# Sheet1.net
KiCad netlist of a schematic drawn in Altium Designer
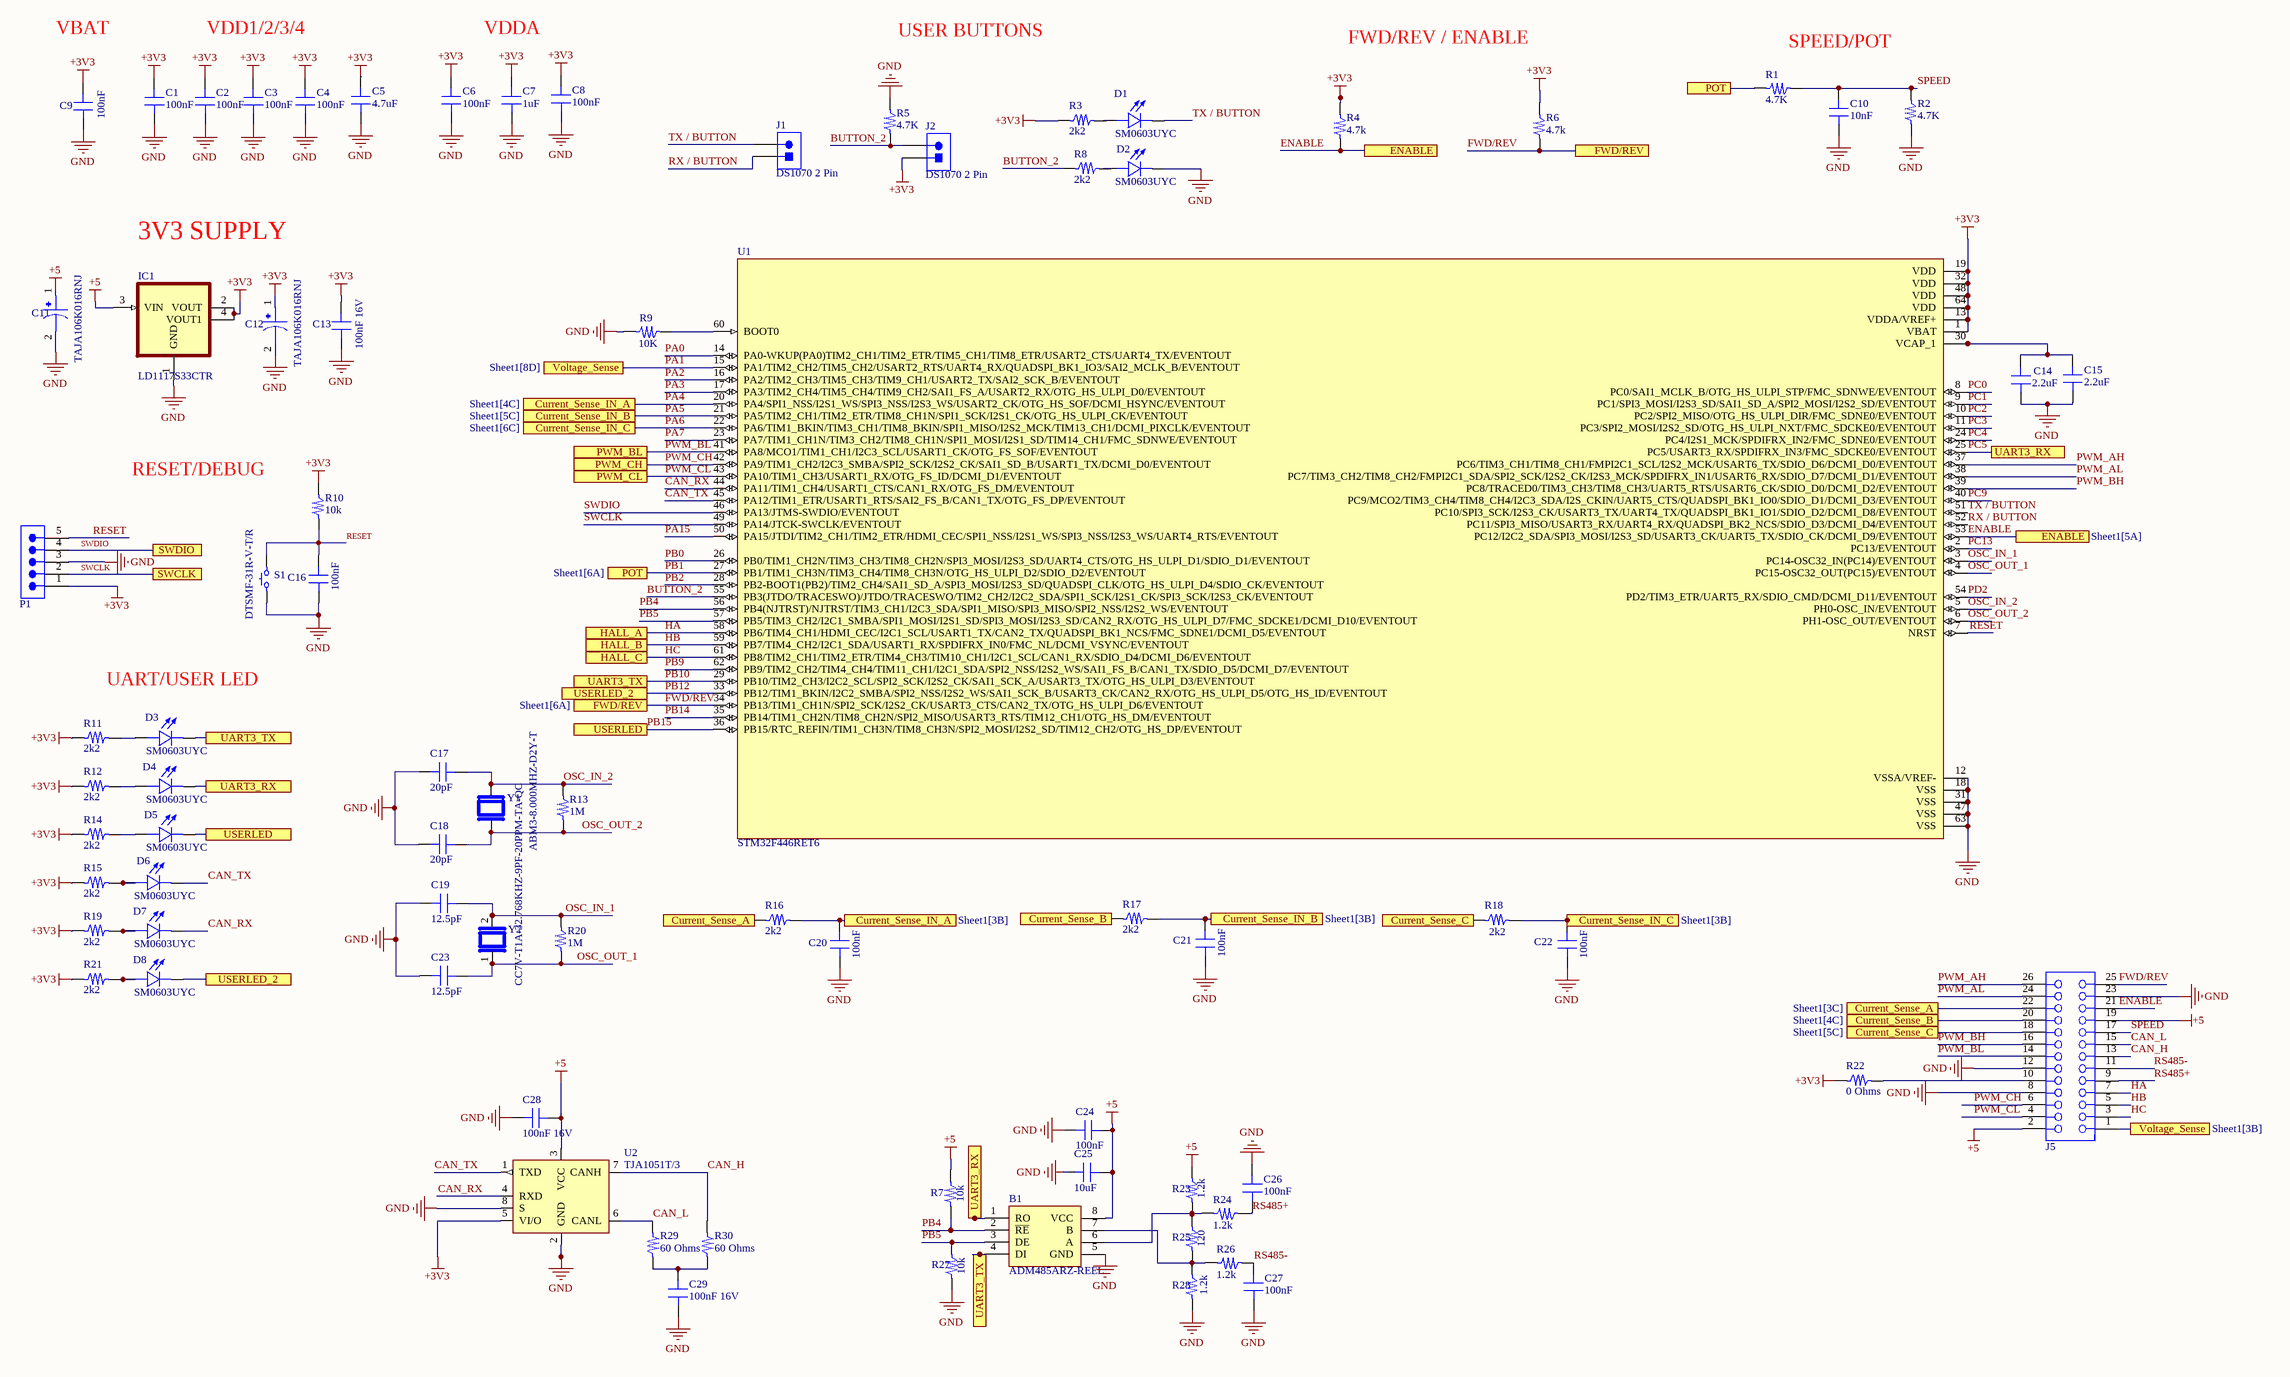
[diagram p0: Sheet1.SchDoc]

(export (version "E")
  (design (tool "Eeschema 10.0.6"))
  (components
    (comp (ref "B1")
      (value "ADM485ARZ-REEL")
      (footprint "SOIC127P600X175-8N")
      (description "RS-422/RS-485 Interface IC RS-485 I/F TRANSCEIVER")
      (fields (field (name "MOUSER PART NUMBER") "584-ADM485ARZ-R"))
      (libsource (lib "ADM485ARZ-REEL") (part "ADM485ARZ-REEL"))
    )
    (comp (ref "C1")
      (value "100nF")
      (footprint "0603_CAP")
      (description "CL10B105KO8NNNC - MLCC (1608) 0603 1uF 16VDC ±10% X7R")
      (libsource (lib "HidroanaSCHLib1") (part "CAP_0603"))
    )
    (comp (ref "C2")
      (value "100nF")
      (footprint "0603_CAP")
      (description "CL10B105KO8NNNC - MLCC (1608) 0603 1uF 16VDC ±10% X7R")
      (libsource (lib "HidroanaSCHLib1") (part "CAP_0603"))
    )
    (comp (ref "C3")
      (value "100nF")
      (footprint "0603_CAP")
      (description "CL10B105KO8NNNC - MLCC (1608) 0603 1uF 16VDC ±10% X7R")
      (libsource (lib "HidroanaSCHLib1") (part "CAP_0603"))
    )
    (comp (ref "C4")
      (value "100nF")
      (footprint "0603_CAP")
      (description "CL10B105KO8NNNC - MLCC (1608) 0603 1uF 16VDC ±10% X7R")
      (libsource (lib "HidroanaSCHLib1") (part "CAP_0603"))
    )
    (comp (ref "C5")
      (value "4.7uF")
      (footprint "0603_CAP")
      (description "CL10B105KO8NNNC - MLCC (1608) 0603 1uF 16VDC ±10% X7R")
      (libsource (lib "HidroanaSCHLib1") (part "CAP_0603"))
    )
    (comp (ref "C6")
      (value "100nF")
      (footprint "0603_CAP")
      (description "CL10B105KO8NNNC - MLCC (1608) 0603 1uF 16VDC ±10% X7R")
      (libsource (lib "HidroanaSCHLib1") (part "CAP_0603"))
    )
    (comp (ref "C7")
      (value "1uF")
      (footprint "0603_CAP")
      (description "CL10B105KO8NNNC - MLCC (1608) 0603 1uF 16VDC ±10% X7R")
      (libsource (lib "HidroanaSCHLib1") (part "CAP_0603"))
    )
    (comp (ref "C8")
      (value "100nF")
      (footprint "0603_CAP")
      (description "CL10B105KO8NNNC - MLCC (1608) 0603 1uF 16VDC ±10% X7R")
      (libsource (lib "HidroanaSCHLib1") (part "CAP_0603"))
    )
    (comp (ref "C9")
      (value "100nF")
      (footprint "0603_CAP")
      (description "CL10B105KO8NNNC - MLCC (1608) 0603 1uF 16VDC ±10% X7R")
      (libsource (lib "HidroanaSCHLib1") (part "CAP_0603"))
    )
    (comp (ref "C10")
      (value "10nF")
      (footprint "0603_CAP")
      (description "CL10B105KO8NNNC - MLCC (1608) 0603 1uF 16VDC ±10% X7R")
      (libsource (lib "HidroanaSCHLib1") (part "CAP_0603"))
    )
    (comp (ref "C11")
      (value "TAJA106K016RNJ")
      (footprint "CAPMP3216X180N")
      (description "10ÂµF Molded Tantalum Capacitors 16V 1206 (3216 Metric) 3Ohm")
      (fields (field (name "MF") "AVX"))
      (libsource (lib "TAJA106K016RNJ") (part "TAJA106K016RNJ"))
    )
    (comp (ref "C12")
      (value "TAJA106K016RNJ")
      (footprint "CAPMP3216X180N")
      (description "10ÂµF Molded Tantalum Capacitors 16V 1206 (3216 Metric) 3Ohm")
      (fields (field (name "MF") "AVX"))
      (libsource (lib "TAJA106K016RNJ") (part "TAJA106K016RNJ"))
    )
    (comp (ref "C13")
      (value "100nF 16V")
      (footprint "0805_CAP")
      (libsource (lib "HidroanaSCHLib") (part "CAP_0805"))
    )
    (comp (ref "C14")
      (value "2.2uF")
      (footprint "0603_CAP")
      (description "CL10B105KO8NNNC - MLCC (1608) 0603 1uF 16VDC ±10% X7R")
      (libsource (lib "HidroanaSCHLib1") (part "CAP_0603"))
    )
    (comp (ref "C15")
      (value "2.2uF")
      (footprint "0603_CAP")
      (description "CL10B105KO8NNNC - MLCC (1608) 0603 1uF 16VDC ±10% X7R")
      (libsource (lib "HidroanaSCHLib1") (part "CAP_0603"))
    )
    (comp (ref "C16")
      (value "100nF")
      (footprint "0603_CAP")
      (description "CL10B105KO8NNNC - MLCC (1608) 0603 1uF 16VDC ±10% X7R")
      (libsource (lib "HidroanaSCHLib1") (part "CAP_0603"))
    )
    (comp (ref "C17")
      (value "20pF")
      (footprint "0603_CAP")
      (description "CL10B105KO8NNNC - MLCC (1608) 0603 1uF 16VDC ±10% X7R")
      (libsource (lib "HidroanaSCHLib1") (part "CAP_0603"))
    )
    (comp (ref "C18")
      (value "20pF")
      (footprint "0603_CAP")
      (description "CL10B105KO8NNNC - MLCC (1608) 0603 1uF 16VDC ±10% X7R")
      (libsource (lib "HidroanaSCHLib1") (part "CAP_0603"))
    )
    (comp (ref "C19")
      (value "12.5pF")
      (footprint "0603_CAP")
      (description "CL10B105KO8NNNC - MLCC (1608) 0603 1uF 16VDC ±10% X7R")
      (libsource (lib "HidroanaSCHLib1") (part "CAP_0603"))
    )
    (comp (ref "C20")
      (value "100nF")
      (footprint "0603_CAP")
      (description "CL10B105KO8NNNC - MLCC (1608) 0603 1uF 16VDC ±10% X7R")
      (libsource (lib "HidroanaSCHLib1") (part "CAP_0603"))
    )
    (comp (ref "C21")
      (value "100nF")
      (footprint "0603_CAP")
      (description "CL10B105KO8NNNC - MLCC (1608) 0603 1uF 16VDC ±10% X7R")
      (libsource (lib "HidroanaSCHLib1") (part "CAP_0603"))
    )
    (comp (ref "C22")
      (value "100nF")
      (footprint "0603_CAP")
      (description "CL10B105KO8NNNC - MLCC (1608) 0603 1uF 16VDC ±10% X7R")
      (libsource (lib "HidroanaSCHLib1") (part "CAP_0603"))
    )
    (comp (ref "C23")
      (value "12.5pF")
      (footprint "0603_CAP")
      (description "CL10B105KO8NNNC - MLCC (1608) 0603 1uF 16VDC ±10% X7R")
      (libsource (lib "HidroanaSCHLib1") (part "CAP_0603"))
    )
    (comp (ref "C24")
      (value "100nF")
      (footprint "0603_CAP")
      (description "CL10B105KO8NNNC - MLCC (1608) 0603 1uF 16VDC ±10% X7R")
      (libsource (lib "HidroanaSCHLib1") (part "CAP_0603"))
    )
    (comp (ref "C25")
      (value "10uF")
      (footprint "0603_CAP")
      (description "CL10B105KO8NNNC - MLCC (1608) 0603 1uF 16VDC ±10% X7R")
      (libsource (lib "HidroanaSCHLib1") (part "CAP_0603"))
    )
    (comp (ref "C26")
      (value "100nF")
      (footprint "0603_CAP")
      (description "CL10B105KO8NNNC - MLCC (1608) 0603 1uF 16VDC ±10% X7R")
      (libsource (lib "HidroanaSCHLib1") (part "CAP_0603"))
    )
    (comp (ref "C27")
      (value "100nF")
      (footprint "0603_CAP")
      (description "CL10B105KO8NNNC - MLCC (1608) 0603 1uF 16VDC ±10% X7R")
      (libsource (lib "HidroanaSCHLib1") (part "CAP_0603"))
    )
    (comp (ref "C28")
      (value "100nF 16V")
      (footprint "0603_CAP")
      (description "CL10B105KO8NNNC - MLCC (1608) 0603 1uF 16VDC ±10% X7R")
      (libsource (lib "HidroanaSCHLib") (part "CAP_0603"))
    )
    (comp (ref "C29")
      (value "100nF 16V")
      (footprint "0603_CAP")
      (description "CL10B105KO8NNNC - MLCC (1608) 0603 1uF 16VDC ±10% X7R")
      (libsource (lib "HidroanaSCHLib") (part "CAP_0603"))
    )
    (comp (ref "D1")
      (value "SM0603UYC")
      (footprint "LED_SM0603UYC")
      (fields (field (name "MF") "Bivar"))
      (libsource (lib "SM0603UYC") (part "SM0603UYC"))
    )
    (comp (ref "D2")
      (value "SM0603UYC")
      (footprint "LED_SM0603UYC")
      (fields (field (name "MF") "Bivar"))
      (libsource (lib "SM0603UYC") (part "SM0603UYC"))
    )
    (comp (ref "D3")
      (value "SM0603UYC")
      (footprint "LED_SM0603UYC")
      (fields (field (name "MF") "Bivar"))
      (libsource (lib "SM0603UYC") (part "SM0603UYC"))
    )
    (comp (ref "D4")
      (value "SM0603UYC")
      (footprint "LED_SM0603UYC")
      (fields (field (name "MF") "Bivar"))
      (libsource (lib "SM0603UYC") (part "SM0603UYC"))
    )
    (comp (ref "D5")
      (value "SM0603UYC")
      (footprint "LED_SM0603UYC")
      (fields (field (name "MF") "Bivar"))
      (libsource (lib "SM0603UYC") (part "SM0603UYC"))
    )
    (comp (ref "D6")
      (value "SM0603UYC")
      (footprint "LED_SM0603UYC")
      (fields (field (name "MF") "Bivar"))
      (libsource (lib "SM0603UYC") (part "SM0603UYC"))
    )
    (comp (ref "D7")
      (value "SM0603UYC")
      (footprint "LED_SM0603UYC")
      (fields (field (name "MF") "Bivar"))
      (libsource (lib "SM0603UYC") (part "SM0603UYC"))
    )
    (comp (ref "D8")
      (value "SM0603UYC")
      (footprint "LED_SM0603UYC")
      (fields (field (name "MF") "Bivar"))
      (libsource (lib "SM0603UYC") (part "SM0603UYC"))
    )
    (comp (ref "IC1")
      (value "LD1117S33CTR")
      (footprint "SOT223")
      (description "Linear Voltage Regulator IC Positive Fixed 1 Output 800mA SOT-223")
      (fields (field (name "MF") "STMicroelectronics"))
      (libsource (lib "LD1117S33CTR") (part "LD1117S33CTR"))
    )
    (comp (ref "J1")
      (value "DS1070 2 Pin")
      (footprint "2PIN_100mil")
      (description "2pin Socket 100mil")
      (libsource (lib "HidroanaSCHLib1") (part "2 Pin Socket"))
    )
    (comp (ref "J2")
      (value "DS1070 2 Pin")
      (footprint "2PIN_100mil")
      (description "2pin Socket 100mil")
      (libsource (lib "HidroanaSCHLib1") (part "2 Pin Socket"))
    )
    (comp (ref "J5")
      (value "61302621821")
      (footprint "61302621821")
      (description "WR-PHD Socket Header, THT, Vertical, pitch 2.54mm, 2 Row, 26P")
      (fields (field (name "MANUFACTURER") "Wurth Elektronik"))
      (libsource (lib "Altium_WR-PHD (rev24a) (3)") (part "61302621821"))
    )
    (comp (ref "P1")
      (value "61300511121")
      (footprint "61300511121")
      (description "WR-PHD Pin Header, THT, Vertical, pitch 2.54mm, 1 Row, 5P")
      (fields (field (name "MANUFACTURER") "Wurth Elektronik"))
      (libsource (lib "Altium_WR-PHD (rev24a)") (part "61300511121"))
    )
    (comp (ref "R1")
      (value "4.7K")
      (footprint "0603_RES")
      (description "0603")
      (fields (field (name "POWER") "1/8W"))
      (libsource (lib "HidroanaSCHLib") (part "RES_0603"))
    )
    (comp (ref "R2")
      (value "4.7K")
      (footprint "0603_RES")
      (description "0603")
      (fields (field (name "POWER") "1/8W"))
      (libsource (lib "HidroanaSCHLib") (part "RES_0603"))
    )
    (comp (ref "R3")
      (value "2k2")
      (footprint "0603_RES")
      (description "0603")
      (fields (field (name "POWER") "1/8W"))
      (libsource (lib "HidroanaSCHLib") (part "RES_0603"))
    )
    (comp (ref "R4")
      (value "4.7k")
      (footprint "0603_RES")
      (description "0603")
      (fields (field (name "POWER") "1/8W"))
      (libsource (lib "HidroanaSCHLib") (part "RES_0603"))
    )
    (comp (ref "R5")
      (value "4.7K")
      (footprint "0603_RES")
      (description "0603")
      (fields (field (name "POWER") "1/8W"))
      (libsource (lib "HidroanaSCHLib") (part "RES_0603"))
    )
    (comp (ref "R6")
      (value "4.7k")
      (footprint "0603_RES")
      (description "0603")
      (fields (field (name "POWER") "1/8W"))
      (libsource (lib "HidroanaSCHLib") (part "RES_0603"))
    )
    (comp (ref "R7")
      (value "10k")
      (footprint "0603_RES")
      (description "0603")
      (fields (field (name "POWER") "1/8W"))
      (libsource (lib "HidroanaSCHLib") (part "RES_0603"))
    )
    (comp (ref "R8")
      (value "2k2")
      (footprint "0603_RES")
      (description "0603")
      (fields (field (name "POWER") "1/8W"))
      (libsource (lib "HidroanaSCHLib") (part "RES_0603"))
    )
    (comp (ref "R9")
      (value "10K")
      (footprint "0603_RES")
      (description "0603")
      (fields (field (name "POWER") "1/8W"))
      (libsource (lib "HidroanaSCHLib") (part "RES_0603"))
    )
    (comp (ref "R10")
      (value "10k")
      (footprint "0603_RES")
      (description "0603")
      (fields (field (name "POWER") "1/8W"))
      (libsource (lib "HidroanaSCHLib") (part "RES_0603"))
    )
    (comp (ref "R11")
      (value "2k2")
      (footprint "0603_RES")
      (description "0603")
      (fields (field (name "POWER") "1/8W"))
      (libsource (lib "HidroanaSCHLib") (part "RES_0603"))
    )
    (comp (ref "R12")
      (value "2k2")
      (footprint "0603_RES")
      (description "0603")
      (fields (field (name "POWER") "1/8W"))
      (libsource (lib "HidroanaSCHLib") (part "RES_0603"))
    )
    (comp (ref "R13")
      (value "1M")
      (footprint "0603_RES")
      (description "0603")
      (fields (field (name "POWER") "1/8W"))
      (libsource (lib "HidroanaSCHLib") (part "RES_0603"))
    )
    (comp (ref "R14")
      (value "2k2")
      (footprint "0603_RES")
      (description "0603")
      (fields (field (name "POWER") "1/8W"))
      (libsource (lib "HidroanaSCHLib") (part "RES_0603"))
    )
    (comp (ref "R15")
      (value "2k2")
      (footprint "0603_RES")
      (description "0603")
      (fields (field (name "POWER") "1/8W"))
      (libsource (lib "HidroanaSCHLib") (part "RES_0603"))
    )
    (comp (ref "R16")
      (value "2k2")
      (footprint "0603_RES")
      (description "0603")
      (fields (field (name "POWER") "1/8W"))
      (libsource (lib "HidroanaSCHLib") (part "RES_0603"))
    )
    (comp (ref "R17")
      (value "2k2")
      (footprint "0603_RES")
      (description "0603")
      (fields (field (name "POWER") "1/8W"))
      (libsource (lib "HidroanaSCHLib") (part "RES_0603"))
    )
    (comp (ref "R18")
      (value "2k2")
      (footprint "0603_RES")
      (description "0603")
      (fields (field (name "POWER") "1/8W"))
      (libsource (lib "HidroanaSCHLib") (part "RES_0603"))
    )
    (comp (ref "R19")
      (value "2k2")
      (footprint "0603_RES")
      (description "0603")
      (fields (field (name "POWER") "1/8W"))
      (libsource (lib "HidroanaSCHLib") (part "RES_0603"))
    )
    (comp (ref "R20")
      (value "1M")
      (footprint "0603_RES")
      (description "0603")
      (fields (field (name "POWER") "1/8W"))
      (libsource (lib "HidroanaSCHLib") (part "RES_0603"))
    )
    (comp (ref "R21")
      (value "2k2")
      (footprint "0603_RES")
      (description "0603")
      (fields (field (name "POWER") "1/8W"))
      (libsource (lib "HidroanaSCHLib") (part "RES_0603"))
    )
    (comp (ref "R22")
      (value "0 Ohms")
      (footprint "0805_RES")
      (description "0805")
      (fields (field (name "POWER") "1/8 W"))
      (libsource (lib "HidroanaSCHLib") (part "RES_0805"))
    )
    (comp (ref "R23")
      (value "1.2k")
      (footprint "0603_RES")
      (description "0603")
      (fields (field (name "POWER") "1/8W"))
      (libsource (lib "HidroanaSCHLib") (part "RES_0603"))
    )
    (comp (ref "R24")
      (value "1.2k")
      (footprint "0603_RES")
      (description "0603")
      (fields (field (name "POWER") "1/8W"))
      (libsource (lib "HidroanaSCHLib") (part "RES_0603"))
    )
    (comp (ref "R25")
      (value "120")
      (footprint "0603_RES")
      (description "0603")
      (fields (field (name "POWER") "1/8W"))
      (libsource (lib "HidroanaSCHLib") (part "RES_0603"))
    )
    (comp (ref "R26")
      (value "1.2k")
      (footprint "0603_RES")
      (description "0603")
      (fields (field (name "POWER") "1/8W"))
      (libsource (lib "HidroanaSCHLib") (part "RES_0603"))
    )
    (comp (ref "R27")
      (value "10k")
      (footprint "0603_RES")
      (description "0603")
      (fields (field (name "POWER") "1/8W"))
      (libsource (lib "HidroanaSCHLib") (part "RES_0603"))
    )
    (comp (ref "R28")
      (value "1.2k")
      (footprint "0603_RES")
      (description "0603")
      (fields (field (name "POWER") "1/8W"))
      (libsource (lib "HidroanaSCHLib") (part "RES_0603"))
    )
    (comp (ref "R29")
      (value "60 Ohms")
      (footprint "0603_RES")
      (libsource (lib "HidroanaSCHLib") (part "1k Ohms"))
    )
    (comp (ref "R30")
      (value "60 Ohms")
      (footprint "0603_RES")
      (libsource (lib "HidroanaSCHLib") (part "1k Ohms"))
    )
    (comp (ref "S1")
      (value "DTSMF-31R-V-T/R")
      (footprint "Button")
      (description "DTSMF-31R-V-T/R - SWITCH TACT 6.00x3.50 4.30mm 260gF SMT V/T")
      (libsource (lib "HidroanaSCHLib") (part "DTSMF-31R-V-T/R"))
    )
    (comp (ref "U1")
      (value "STM32F446RET6")
      (footprint "QFP50P1200X1200X160-64N")
      (description "MCU 32-Bit STM32 ARM Cortex M4 RISC 512KB Flash 2.5V/3.3V 64-Pin LQFP Tray")
      (libsource (lib "STM32F446RET6") (part "STM32F446RET6"))
    )
    (comp (ref "U2")
      (value "TJA1051T/3")
      (footprint "SOT96-1")
      (description "1/1 ÐŸÑ€Ð¸ÐµÐ¼Ð¾Ð¿ÐµÑ€ÐµÐ´Ð°Ñ‚Ñ‡Ð¸Ðº ÐŸÐ¾Ð»Ð¾Ð²Ð¸Ð½Ð° CANbus 8-SO")
      (fields (field (name "MF") "NXP USA"))
      (libsource (lib "TJA1051T_3") (part "TJA1051T/3"))
    )
    (comp (ref "Y1")
      (value "ABM3-8.000MHZ-D2Y-T")
      (footprint "XTAL_ABM3-8.000MHZ-D2Y-T")
      (description "8 MHz Â±20ppm Crystal 18pF 140 Ohms 2-SMD, No Lead")
      (fields (field (name "MF") "Abracon"))
      (libsource (lib "ABM3-8.000MHZ-D2Y-T") (part "ABM3-8.000MHZ-D2Y-T"))
    )
    (comp (ref "Y2")
      (value "CC7V-T1A-32.768KHZ-9PF-20PPM-TA-QC")
      (footprint "XTAL_CC7V-T1A-32.768KHZ-9PF-20PPM-TA-QC")
      (description "LOW FREQUENCY CRYSTAL")
      (fields (field (name "MF") "Micro Crystal") (field (name "MP") "CC7V-T1A-32.768kHz-9pF-20PPM-TA-QC"))
      (libsource (lib "CC7V-T1A-32.768KHZ-9PF-20PPM-TA-QC") (part "CC7V-T1A-32.768KHZ-9PF-20PPM-TA-QC"))
    )
  )
  (nets
    (net (code "1") (name "+3V3") (class "Default")
      (node (ref "C1") (pin "1") (pinfunction "1_1") (pintype "passive"))
      (node (ref "C12") (pin "1") (pinfunction "1_1") (pintype "passive"))
      (node (ref "C13") (pin "2") (pinfunction "2_2") (pintype "passive"))
      (node (ref "C2") (pin "1") (pinfunction "1_1") (pintype "passive"))
      (node (ref "C3") (pin "1") (pinfunction "1_1") (pintype "passive"))
      (node (ref "C4") (pin "1") (pinfunction "1_1") (pintype "passive"))
      (node (ref "C5") (pin "1") (pinfunction "1_1") (pintype "passive"))
      (node (ref "C6") (pin "1") (pinfunction "1_1") (pintype "passive"))
      (node (ref "C7") (pin "1") (pinfunction "1_1") (pintype "passive"))
      (node (ref "C8") (pin "1") (pinfunction "1_1") (pintype "passive"))
      (node (ref "C9") (pin "1") (pinfunction "1_1") (pintype "passive"))
      (node (ref "IC1") (pin "2") (pinfunction "VOUT_2") (pintype "power_in"))
      (node (ref "IC1") (pin "4") (pinfunction "VOUT1_4") (pintype "power_in"))
      (node (ref "J2") (pin "1") (pintype "passive"))
      (node (ref "P1") (pin "1") (pinfunction "1_1") (pintype "passive"))
      (node (ref "R10") (pin "2") (pintype "passive"))
      (node (ref "R11") (pin "1") (pintype "passive"))
      (node (ref "R12") (pin "1") (pintype "passive"))
      (node (ref "R14") (pin "1") (pintype "passive"))
      (node (ref "R15") (pin "1") (pintype "passive"))
      (node (ref "R19") (pin "1") (pintype "passive"))
      (node (ref "R21") (pin "1") (pintype "passive"))
      (node (ref "R22") (pin "1") (pintype "passive"))
      (node (ref "R3") (pin "1") (pintype "passive"))
      (node (ref "R4") (pin "2") (pintype "passive"))
      (node (ref "R6") (pin "2") (pintype "passive"))
      (node (ref "U1") (pin "1") (pinfunction "VBAT_1") (pintype "power_in"))
      (node (ref "U1") (pin "13") (pinfunction "VDDA/VREF+_13") (pintype "power_in"))
      (node (ref "U1") (pin "19") (pinfunction "VDD_19") (pintype "power_in"))
      (node (ref "U1") (pin "32") (pinfunction "VDD_32") (pintype "power_in"))
      (node (ref "U1") (pin "48") (pinfunction "VDD_48") (pintype "power_in"))
      (node (ref "U1") (pin "64") (pinfunction "VDD_64") (pintype "power_in"))
      (node (ref "U2") (pin "5") (pinfunction "VI/O_5") (pintype "passive"))
    )
    (net (code "2") (name "+5") (class "Default")
      (node (ref "B1") (pin "8") (pinfunction "VCC_8") (pintype "passive"))
      (node (ref "C11") (pin "1") (pinfunction "1_1") (pintype "passive"))
      (node (ref "C24") (pin "1") (pinfunction "1_1") (pintype "passive"))
      (node (ref "C25") (pin "1") (pinfunction "1_1") (pintype "passive"))
      (node (ref "C28") (pin "2") (pinfunction "2_2") (pintype "passive"))
      (node (ref "IC1") (pin "3") (pinfunction "VIN_3") (pintype "input"))
      (node (ref "J5") (pin "19") (pinfunction "19_19") (pintype "passive"))
      (node (ref "J5") (pin "2") (pinfunction "2_2") (pintype "passive"))
      (node (ref "R23") (pin "2") (pintype "passive"))
      (node (ref "R7") (pin "2") (pintype "passive"))
      (node (ref "U2") (pin "3") (pinfunction "VCC_3") (pintype "bidirectional"))
    )
    (net (code "3") (name "/BUTTON_2") (class "Default")
      (node (ref "J2") (pin "2") (pinfunction "2_2") (pintype "passive"))
      (node (ref "R5") (pin "1") (pintype "passive"))
      (node (ref "R8") (pin "1") (pintype "passive"))
      (node (ref "U1") (pin "55") (pinfunction "PB3(JTDO/TRACESWO)/JTDO/TRACESWO/TIM2_CH2/I2C2_SDA/SPI1_SCK/I2S1_CK/SPI3_SCK/I2S3_CK/EVENTOUT_55") (pintype "bidirectional"))
    )
    (net (code "4") (name "/CAN_H") (class "Default")
      (node (ref "J5") (pin "13") (pinfunction "13_13") (pintype "passive"))
      (node (ref "R30") (pin "1") (pintype "passive"))
      (node (ref "U2") (pin "7") (pinfunction "CANH_7") (pintype "bidirectional"))
    )
    (net (code "5") (name "/CAN_L") (class "Default")
      (node (ref "J5") (pin "15") (pinfunction "15_15") (pintype "passive"))
      (node (ref "R29") (pin "1") (pintype "passive"))
      (node (ref "U2") (pin "6") (pinfunction "CANL_6") (pintype "bidirectional"))
    )
    (net (code "6") (name "/CAN_RX") (class "Default")
      (node (ref "D7") (pin "C") (pinfunction "C_C") (pintype "passive"))
      (node (ref "U1") (pin "44") (pinfunction "PA11/TIM1_CH4/USART1_CTS/CAN1_RX/OTG_FS_DM/EVENTOUT_44") (pintype "bidirectional"))
      (node (ref "U2") (pin "4") (pinfunction "RXD_4") (pintype "bidirectional"))
    )
    (net (code "7") (name "/CAN_TX") (class "Default")
      (node (ref "D6") (pin "C") (pinfunction "C_C") (pintype "passive"))
      (node (ref "U1") (pin "45") (pinfunction "PA12/TIM1_ETR/USART1_RTS/SAI2_FS_B/CAN1_TX/OTG_FS_DP/EVENTOUT_45") (pintype "bidirectional"))
      (node (ref "U2") (pin "1") (pinfunction "TXD_1") (pintype "output"))
    )
    (net (code "8") (name "/Current_Sense_A") (class "Default")
      (node (ref "J5") (pin "22") (pinfunction "22_22") (pintype "passive"))
      (node (ref "R16") (pin "1") (pintype "passive"))
    )
    (net (code "9") (name "/Current_Sense_B") (class "Default")
      (node (ref "J5") (pin "20") (pinfunction "20_20") (pintype "passive"))
      (node (ref "R17") (pin "1") (pintype "passive"))
    )
    (net (code "10") (name "/Current_Sense_C") (class "Default")
      (node (ref "J5") (pin "18") (pinfunction "18_18") (pintype "passive"))
      (node (ref "R18") (pin "1") (pintype "passive"))
    )
    (net (code "11") (name "/ENABLE") (class "Default")
      (node (ref "J5") (pin "21") (pinfunction "21_21") (pintype "passive"))
      (node (ref "R4") (pin "1") (pintype "passive"))
      (node (ref "U1") (pin "53") (pinfunction "PC12/I2C2_SDA/SPI3_MOSI/I2S3_SD/USART3_CK/UART5_TX/SDIO_CK/DCMI_D9/EVENTOUT_53") (pintype "bidirectional"))
    )
    (net (code "12") (name "/FWD{slash}REV") (class "Default")
      (node (ref "J5") (pin "25") (pinfunction "25_25") (pintype "passive"))
      (node (ref "R6") (pin "1") (pintype "passive"))
      (node (ref "U1") (pin "34") (pinfunction "PB13/TIM1_CH1N/SPI2_SCK/I2S2_CK/USART3_CTS/CAN2_TX/OTG_HS_ULPI_D6/EVENTOUT_34") (pintype "bidirectional"))
    )
    (net (code "13") (name "/HA") (class "Default")
      (node (ref "J5") (pin "7") (pinfunction "7_7") (pintype "passive"))
      (node (ref "U1") (pin "58") (pinfunction "PB6/TIM4_CH1/HDMI_CEC/I2C1_SCL/USART1_TX/CAN2_TX/QUADSPI_BK1_NCS/FMC_SDNE1/DCMI_D5/EVENTOUT_58") (pintype "bidirectional"))
    )
    (net (code "14") (name "/HB") (class "Default")
      (node (ref "J5") (pin "5") (pinfunction "5_5") (pintype "passive"))
      (node (ref "U1") (pin "59") (pinfunction "PB7/TIM4_CH2/I2C1_SDA/USART1_RX/SPDIFRX_IN0/FMC_NL/DCMI_VSYNC/EVENTOUT_59") (pintype "bidirectional"))
    )
    (net (code "15") (name "/HC") (class "Default")
      (node (ref "J5") (pin "3") (pinfunction "3_3") (pintype "passive"))
      (node (ref "U1") (pin "61") (pinfunction "PB8/TIM2_CH1/TIM2_ETR/TIM4_CH3/TIM10_CH1/I2C1_SCL/CAN1_RX/SDIO_D4/DCMI_D6/EVENTOUT_61") (pintype "bidirectional"))
    )
    (net (code "16") (name "/OSC_IN_1") (class "Default")
      (node (ref "C19") (pin "2") (pinfunction "2_2") (pintype "passive"))
      (node (ref "R20") (pin "2") (pintype "passive"))
      (node (ref "U1") (pin "3") (pinfunction "PC14-OSC32_IN(PC14)/EVENTOUT_3") (pintype "bidirectional"))
      (node (ref "Y2") (pin "2") (pinfunction "2_2") (pintype "passive"))
    )
    (net (code "17") (name "/OSC_IN_2") (class "Default")
      (node (ref "C17") (pin "2") (pinfunction "2_2") (pintype "passive"))
      (node (ref "R13") (pin "2") (pintype "passive"))
      (node (ref "U1") (pin "5") (pinfunction "PH0-OSC_IN/EVENTOUT_5") (pintype "bidirectional"))
      (node (ref "Y1") (pin "2") (pinfunction "2_2") (pintype "passive"))
    )
    (net (code "18") (name "/OSC_OUT_1") (class "Default")
      (node (ref "C23") (pin "2") (pinfunction "2_2") (pintype "passive"))
      (node (ref "R20") (pin "1") (pintype "passive"))
      (node (ref "U1") (pin "4") (pinfunction "PC15-OSC32_OUT(PC15)/EVENTOUT_4") (pintype "bidirectional"))
      (node (ref "Y2") (pin "1") (pinfunction "1_1") (pintype "passive"))
    )
    (net (code "19") (name "/OSC_OUT_2") (class "Default")
      (node (ref "C18") (pin "2") (pinfunction "2_2") (pintype "passive"))
      (node (ref "R13") (pin "1") (pintype "passive"))
      (node (ref "U1") (pin "6") (pinfunction "PH1-OSC_OUT/EVENTOUT_6") (pintype "bidirectional"))
      (node (ref "Y1") (pin "1") (pinfunction "1_1") (pintype "passive"))
    )
    (net (code "20") (name "/PA0") (class "Default")
      (node (ref "U1") (pin "14") (pinfunction "PA0-WKUP(PA0)TIM2_CH1/TIM2_ETR/TIM5_CH1/TIM8_ETR/USART2_CTS/UART4_TX/EVENTOUT_14") (pintype "bidirectional"))
    )
    (net (code "21") (name "/PA1") (class "Default")
      (node (ref "J5") (pin "1") (pinfunction "1_1") (pintype "passive"))
      (node (ref "U1") (pin "15") (pinfunction "PA1/TIM2_CH2/TIM5_CH2/USART2_RTS/UART4_RX/QUADSPI_BK1_IO3/SAI2_MCLK_B/EVENTOUT_15") (pintype "bidirectional"))
    )
    (net (code "22") (name "/PA2") (class "Default")
      (node (ref "U1") (pin "16") (pinfunction "PA2/TIM2_CH3/TIM5_CH3/TIM9_CH1/USART2_TX/SAI2_SCK_B/EVENTOUT_16") (pintype "bidirectional"))
    )
    (net (code "23") (name "/PA3") (class "Default")
      (node (ref "U1") (pin "17") (pinfunction "PA3/TIM2_CH4/TIM5_CH4/TIM9_CH2/SAI1_FS_A/USART2_RX/OTG_HS_ULPI_D0/EVENTOUT_17") (pintype "bidirectional"))
    )
    (net (code "24") (name "/PA4") (class "Default")
      (node (ref "C20") (pin "1") (pinfunction "1_1") (pintype "passive"))
      (node (ref "R16") (pin "2") (pintype "passive"))
      (node (ref "U1") (pin "20") (pinfunction "PA4/SPI1_NSS/I2S1_WS/SPI3_NSS/I2S3_WS/USART2_CK/OTG_HS_SOF/DCMI_HSYNC/EVENTOUT_20") (pintype "bidirectional"))
    )
    (net (code "25") (name "/PA5") (class "Default")
      (node (ref "C21") (pin "1") (pinfunction "1_1") (pintype "passive"))
      (node (ref "R17") (pin "2") (pintype "passive"))
      (node (ref "U1") (pin "21") (pinfunction "PA5/TIM2_CH1/TIM2_ETR/TIM8_CH1N/SPI1_SCK/I2S1_CK/OTG_HS_ULPI_CK/EVENTOUT_21") (pintype "bidirectional"))
    )
    (net (code "26") (name "/PA6") (class "Default")
      (node (ref "C22") (pin "1") (pinfunction "1_1") (pintype "passive"))
      (node (ref "R18") (pin "2") (pintype "passive"))
      (node (ref "U1") (pin "22") (pinfunction "PA6/TIM1_BKIN/TIM3_CH1/TIM8_BKIN/SPI1_MISO/I2S2_MCK/TIM13_CH1/DCMI_PIXCLK/EVENTOUT_22") (pintype "bidirectional"))
    )
    (net (code "27") (name "/PA7") (class "Default")
      (node (ref "U1") (pin "23") (pinfunction "PA7/TIM1_CH1N/TIM3_CH2/TIM8_CH1N/SPI1_MOSI/I2S1_SD/TIM14_CH1/FMC_SDNWE/EVENTOUT_23") (pintype "bidirectional"))
    )
    (net (code "28") (name "/PA15") (class "Default")
      (node (ref "U1") (pin "50") (pinfunction "PA15/JTDI/TIM2_CH1/TIM2_ETR/HDMI_CEC/SPI1_NSS/I2S1_WS/SPI3_NSS/I2S3_WS/UART4_RTS/EVENTOUT_50") (pintype "bidirectional"))
    )
    (net (code "29") (name "/PB0") (class "Default")
      (node (ref "U1") (pin "26") (pinfunction "PB0/TIM1_CH2N/TIM3_CH3/TIM8_CH2N/SPI3_MOSI/I2S3_SD/UART4_CTS/OTG_HS_ULPI_D1/SDIO_D1/EVENTOUT_26") (pintype "bidirectional"))
    )
    (net (code "30") (name "/PB1") (class "Default")
      (node (ref "R1") (pin "2") (pintype "passive"))
      (node (ref "U1") (pin "27") (pinfunction "PB1/TIM1_CH3N/TIM3_CH4/TIM8_CH3N/OTG_HS_ULPI_D2/SDIO_D2/EVENTOUT_27") (pintype "bidirectional"))
    )
    (net (code "31") (name "/PB2") (class "Default")
      (node (ref "U1") (pin "28") (pinfunction "PB2-BOOT1(PB2)/TIM2_CH4/SAI1_SD_A/SPI3_MOSI/I2S3_SD/QUADSPI_CLK/OTG_HS_ULPI_D4/SDIO_CK/EVENTOUT_28") (pintype "bidirectional"))
    )
    (net (code "32") (name "/PB4") (class "Default")
      (node (ref "B1") (pin "2") (pinfunction "~{RE}_2") (pintype "passive"))
      (node (ref "R7") (pin "1") (pintype "passive"))
      (node (ref "U1") (pin "56") (pinfunction "PB4(NJTRST)/NJTRST/TIM3_CH1/I2C3_SDA/SPI1_MISO/SPI3_MISO/SPI2_NSS/I2S2_WS/EVENTOUT_56") (pintype "bidirectional"))
    )
    (net (code "33") (name "/PB5") (class "Default")
      (node (ref "B1") (pin "3") (pinfunction "DE_3") (pintype "passive"))
      (node (ref "R27") (pin "2") (pintype "passive"))
      (node (ref "U1") (pin "57") (pinfunction "PB5/TIM3_CH2/I2C1_SMBA/SPI1_MOSI/I2S1_SD/SPI3_MOSI/I2S3_SD/CAN2_RX/OTG_HS_ULPI_D7/FMC_SDCKE1/DCMI_D10/EVENTOUT_57") (pintype "bidirectional"))
    )
    (net (code "34") (name "/PB9") (class "Default")
      (node (ref "U1") (pin "62") (pinfunction "PB9/TIM2_CH2/TIM4_CH4/TIM11_CH1/I2C1_SDA/SPI2_NSS/I2S2_WS/SAI1_FS_B/CAN1_TX/SDIO_D5/DCMI_D7/EVENTOUT_62") (pintype "bidirectional"))
    )
    (net (code "35") (name "/PB10") (class "Default")
      (node (ref "B1") (pin "4") (pinfunction "DI_4") (pintype "passive"))
      (node (ref "D3") (pin "C") (pinfunction "C_C") (pintype "passive"))
      (node (ref "U1") (pin "29") (pinfunction "PB10/TIM2_CH3/I2C2_SCL/SPI2_SCK/I2S2_CK/SAI1_SCK_A/USART3_TX/OTG_HS_ULPI_D3/EVENTOUT_29") (pintype "bidirectional"))
    )
    (net (code "36") (name "/PB12") (class "Default")
      (node (ref "D8") (pin "C") (pinfunction "C_C") (pintype "passive"))
      (node (ref "U1") (pin "33") (pinfunction "PB12/TIM1_BKIN/I2C2_SMBA/SPI2_NSS/I2S2_WS/SAI1_SCK_B/USART3_CK/CAN2_RX/OTG_HS_ULPI_D5/OTG_HS_ID/EVENTOUT_33") (pintype "bidirectional"))
    )
    (net (code "37") (name "/PB14") (class "Default")
      (node (ref "U1") (pin "35") (pinfunction "PB14/TIM1_CH2N/TIM8_CH2N/SPI2_MISO/USART3_RTS/TIM12_CH1/OTG_HS_DM/EVENTOUT_35") (pintype "bidirectional"))
    )
    (net (code "38") (name "/PB15") (class "Default")
      (node (ref "D5") (pin "C") (pinfunction "C_C") (pintype "passive"))
      (node (ref "U1") (pin "36") (pinfunction "PB15/RTC_REFIN/TIM1_CH3N/TIM8_CH3N/SPI2_MOSI/I2S2_SD/TIM12_CH2/OTG_HS_DP/EVENTOUT_36") (pintype "bidirectional"))
    )
    (net (code "39") (name "/PC0") (class "Default")
      (node (ref "U1") (pin "8") (pinfunction "PC0/SAI1_MCLK_B/OTG_HS_ULPI_STP/FMC_SDNWE/EVENTOUT_8") (pintype "bidirectional"))
    )
    (net (code "40") (name "/PC1") (class "Default")
      (node (ref "U1") (pin "9") (pinfunction "PC1/SPI3_MOSI/I2S3_SD/SAI1_SD_A/SPI2_MOSI/I2S2_SD/EVENTOUT_9") (pintype "bidirectional"))
    )
    (net (code "41") (name "/PC2") (class "Default")
      (node (ref "U1") (pin "10") (pinfunction "PC2/SPI2_MISO/OTG_HS_ULPI_DIR/FMC_SDNE0/EVENTOUT_10") (pintype "bidirectional"))
    )
    (net (code "42") (name "/PC3") (class "Default")
      (node (ref "U1") (pin "11") (pinfunction "PC3/SPI2_MOSI/I2S2_SD/OTG_HS_ULPI_NXT/FMC_SDCKE0/EVENTOUT_11") (pintype "bidirectional"))
    )
    (net (code "43") (name "/PC4") (class "Default")
      (node (ref "U1") (pin "24") (pinfunction "PC4/I2S1_MCK/SPDIFRX_IN2/FMC_SDNE0/EVENTOUT_24") (pintype "bidirectional"))
    )
    (net (code "44") (name "/PC5") (class "Default")
      (node (ref "B1") (pin "1") (pinfunction "RO_1") (pintype "passive"))
      (node (ref "D4") (pin "C") (pinfunction "C_C") (pintype "passive"))
      (node (ref "U1") (pin "25") (pinfunction "PC5/USART3_RX/SPDIFRX_IN3/FMC_SDCKE0/EVENTOUT_25") (pintype "bidirectional"))
    )
    (net (code "45") (name "/PC9") (class "Default")
      (node (ref "U1") (pin "40") (pinfunction "PC9/MCO2/TIM3_CH4/TIM8_CH4/I2C3_SDA/I2S_CKIN/UART5_CTS/QUADSPI_BK1_IO0/SDIO_D1/DCMI_D3/EVENTOUT_40") (pintype "bidirectional"))
    )
    (net (code "46") (name "/PC13") (class "Default")
      (node (ref "U1") (pin "2") (pinfunction "PC13/EVENTOUT_2") (pintype "bidirectional"))
    )
    (net (code "47") (name "/PD2") (class "Default")
      (node (ref "U1") (pin "54") (pinfunction "PD2/TIM3_ETR/UART5_RX/SDIO_CMD/DCMI_D11/EVENTOUT_54") (pintype "bidirectional"))
    )
    (net (code "48") (name "/PWM_AH") (class "Default")
      (node (ref "J5") (pin "26") (pinfunction "26_26") (pintype "passive"))
      (node (ref "U1") (pin "37") (pinfunction "PC6/TIM3_CH1/TIM8_CH1/FMPI2C1_SCL/I2S2_MCK/USART6_TX/SDIO_D6/DCMI_D0/EVENTOUT_37") (pintype "bidirectional"))
    )
    (net (code "49") (name "/PWM_AL") (class "Default")
      (node (ref "J5") (pin "24") (pinfunction "24_24") (pintype "passive"))
      (node (ref "U1") (pin "38") (pinfunction "PC7/TIM3_CH2/TIM8_CH2/FMPI2C1_SDA/SPI2_SCK/I2S2_CK/I2S3_MCK/SPDIFRX_IN1/USART6_RX/SDIO_D7/DCMI_D1/EVENTOUT_38") (pintype "bidirectional"))
    )
    (net (code "50") (name "/PWM_BH") (class "Default")
      (node (ref "J5") (pin "16") (pinfunction "16_16") (pintype "passive"))
      (node (ref "U1") (pin "39") (pinfunction "PC8/TRACED0/TIM3_CH3/TIM8_CH3/UART5_RTS/USART6_CK/SDIO_D0/DCMI_D2/EVENTOUT_39") (pintype "bidirectional"))
    )
    (net (code "51") (name "/PWM_BL") (class "Default")
      (node (ref "J5") (pin "14") (pinfunction "14_14") (pintype "passive"))
      (node (ref "U1") (pin "41") (pinfunction "PA8/MCO1/TIM1_CH1/I2C3_SCL/USART1_CK/OTG_FS_SOF/EVENTOUT_41") (pintype "bidirectional"))
    )
    (net (code "52") (name "/PWM_CH") (class "Default")
      (node (ref "J5") (pin "6") (pinfunction "6_6") (pintype "passive"))
      (node (ref "U1") (pin "42") (pinfunction "PA9/TIM1_CH2/I2C3_SMBA/SPI2_SCK/I2S2_CK/SAI1_SD_B/USART1_TX/DCMI_D0/EVENTOUT_42") (pintype "bidirectional"))
    )
    (net (code "53") (name "/PWM_CL") (class "Default")
      (node (ref "J5") (pin "4") (pinfunction "4_4") (pintype "passive"))
      (node (ref "U1") (pin "43") (pinfunction "PA10/TIM1_CH3/USART1_RX/OTG_FS_ID/DCMI_D1/EVENTOUT_43") (pintype "bidirectional"))
    )
    (net (code "54") (name "/RESET") (class "Default")
      (node (ref "C16") (pin "1") (pinfunction "1_1") (pintype "passive"))
      (node (ref "P1") (pin "5") (pinfunction "5_5") (pintype "passive"))
      (node (ref "R10") (pin "1") (pintype "passive"))
      (node (ref "S1") (pin "2") (pinfunction "2_2") (pintype "passive"))
      (node (ref "U1") (pin "7") (pinfunction "NRST_7") (pintype "bidirectional"))
    )
    (net (code "55") (name "/RS485+") (class "Default")
      (node (ref "C26") (pin "2") (pinfunction "2_2") (pintype "passive"))
      (node (ref "J5") (pin "9") (pinfunction "9_9") (pintype "passive"))
      (node (ref "R24") (pin "1") (pintype "passive"))
    )
    (net (code "56") (name "/RS485-") (class "Default")
      (node (ref "C27") (pin "1") (pinfunction "1_1") (pintype "passive"))
      (node (ref "J5") (pin "11") (pinfunction "11_11") (pintype "passive"))
      (node (ref "R26") (pin "1") (pintype "passive"))
    )
    (net (code "57") (name "/RX {slash} BUTTON") (class "Default")
      (node (ref "J1") (pin "1") (pintype "passive"))
      (node (ref "U1") (pin "52") (pinfunction "PC11/SPI3_MISO/USART3_RX/UART4_RX/QUADSPI_BK2_NCS/SDIO_D3/DCMI_D4/EVENTOUT_52") (pintype "bidirectional"))
    )
    (net (code "58") (name "/SPEED") (class "Default")
      (node (ref "C10") (pin "1") (pinfunction "1_1") (pintype "passive"))
      (node (ref "J5") (pin "17") (pinfunction "17_17") (pintype "passive"))
      (node (ref "R1") (pin "1") (pintype "passive"))
      (node (ref "R2") (pin "2") (pintype "passive"))
    )
    (net (code "59") (name "/SWCLK") (class "Default")
      (node (ref "P1") (pin "2") (pinfunction "2_2") (pintype "passive"))
      (node (ref "U1") (pin "49") (pinfunction "PA14/JTCK-SWCLK/EVENTOUT_49") (pintype "bidirectional"))
    )
    (net (code "60") (name "/SWDIO") (class "Default")
      (node (ref "P1") (pin "4") (pinfunction "4_4") (pintype "passive"))
      (node (ref "U1") (pin "46") (pinfunction "PA13/JTMS-SWDIO/EVENTOUT_46") (pintype "bidirectional"))
    )
    (net (code "61") (name "/TX {slash} BUTTON") (class "Default")
      (node (ref "D1") (pin "C") (pinfunction "C_C") (pintype "passive"))
      (node (ref "J1") (pin "2") (pinfunction "2_2") (pintype "passive"))
      (node (ref "U1") (pin "51") (pinfunction "PC10/SPI3_SCK/I2S3_CK/USART3_TX/UART4_TX/QUADSPI_BK1_IO1/SDIO_D2/DCMI_D8/EVENTOUT_51") (pintype "bidirectional"))
    )
    (net (code "62") (name "GND") (class "Default")
      (node (ref "B1") (pin "5") (pinfunction "GND_5") (pintype "passive"))
      (node (ref "C1") (pin "2") (pinfunction "2_2") (pintype "passive"))
      (node (ref "C10") (pin "2") (pinfunction "2_2") (pintype "passive"))
      (node (ref "C11") (pin "2") (pinfunction "2_2") (pintype "passive"))
      (node (ref "C12") (pin "2") (pinfunction "2_2") (pintype "passive"))
      (node (ref "C13") (pin "1") (pinfunction "1_1") (pintype "passive"))
      (node (ref "C14") (pin "2") (pinfunction "2_2") (pintype "passive"))
      (node (ref "C15") (pin "2") (pinfunction "2_2") (pintype "passive"))
      (node (ref "C16") (pin "2") (pinfunction "2_2") (pintype "passive"))
      (node (ref "C17") (pin "1") (pinfunction "1_1") (pintype "passive"))
      (node (ref "C18") (pin "1") (pinfunction "1_1") (pintype "passive"))
      (node (ref "C19") (pin "1") (pinfunction "1_1") (pintype "passive"))
      (node (ref "C2") (pin "2") (pinfunction "2_2") (pintype "passive"))
      (node (ref "C20") (pin "2") (pinfunction "2_2") (pintype "passive"))
      (node (ref "C21") (pin "2") (pinfunction "2_2") (pintype "passive"))
      (node (ref "C22") (pin "2") (pinfunction "2_2") (pintype "passive"))
      (node (ref "C23") (pin "1") (pinfunction "1_1") (pintype "passive"))
      (node (ref "C24") (pin "2") (pinfunction "2_2") (pintype "passive"))
      (node (ref "C25") (pin "2") (pinfunction "2_2") (pintype "passive"))
      (node (ref "C26") (pin "1") (pinfunction "1_1") (pintype "passive"))
      (node (ref "C27") (pin "2") (pinfunction "2_2") (pintype "passive"))
      (node (ref "C28") (pin "1") (pinfunction "1_1") (pintype "passive"))
      (node (ref "C29") (pin "2") (pinfunction "2_2") (pintype "passive"))
      (node (ref "C3") (pin "2") (pinfunction "2_2") (pintype "passive"))
      (node (ref "C4") (pin "2") (pinfunction "2_2") (pintype "passive"))
      (node (ref "C5") (pin "2") (pinfunction "2_2") (pintype "passive"))
      (node (ref "C6") (pin "2") (pinfunction "2_2") (pintype "passive"))
      (node (ref "C7") (pin "2") (pinfunction "2_2") (pintype "passive"))
      (node (ref "C8") (pin "2") (pinfunction "2_2") (pintype "passive"))
      (node (ref "C9") (pin "2") (pinfunction "2_2") (pintype "passive"))
      (node (ref "D2") (pin "C") (pinfunction "C_C") (pintype "passive"))
      (node (ref "IC1") (pin "1") (pinfunction "GND_1") (pintype "power_in"))
      (node (ref "J5") (pin "12") (pinfunction "12_12") (pintype "passive"))
      (node (ref "J5") (pin "23") (pinfunction "23_23") (pintype "passive"))
      (node (ref "J5") (pin "8") (pinfunction "8_8") (pintype "passive"))
      (node (ref "P1") (pin "3") (pinfunction "3_3") (pintype "passive"))
      (node (ref "R2") (pin "1") (pintype "passive"))
      (node (ref "R27") (pin "1") (pintype "passive"))
      (node (ref "R28") (pin "1") (pintype "passive"))
      (node (ref "R5") (pin "2") (pintype "passive"))
      (node (ref "R9") (pin "2") (pintype "passive"))
      (node (ref "S1") (pin "1") (pinfunction "1_1") (pintype "passive"))
      (node (ref "U1") (pin "12") (pinfunction "VSSA/VREF-_12") (pintype "power_in"))
      (node (ref "U1") (pin "18") (pinfunction "VSS_18") (pintype "power_in"))
      (node (ref "U1") (pin "31") (pinfunction "VSS_31") (pintype "power_in"))
      (node (ref "U1") (pin "47") (pinfunction "VSS_47") (pintype "power_in"))
      (node (ref "U1") (pin "63") (pinfunction "VSS_63") (pintype "power_in"))
      (node (ref "U2") (pin "2") (pinfunction "GND_2") (pintype "bidirectional"))
      (node (ref "U2") (pin "8") (pinfunction "S_8") (pintype "power_in"))
    )
    (net (code "63") (name "Net-(B1-A)") (class "Default")
      (node (ref "B1") (pin "6") (pinfunction "A_6") (pintype "passive"))
      (node (ref "R23") (pin "1") (pintype "passive"))
      (node (ref "R24") (pin "2") (pintype "passive"))
      (node (ref "R25") (pin "2") (pintype "passive"))
    )
    (net (code "64") (name "Net-(B1-B)") (class "Default")
      (node (ref "B1") (pin "7") (pinfunction "B_7") (pintype "passive"))
      (node (ref "R25") (pin "1") (pintype "passive"))
      (node (ref "R26") (pin "2") (pintype "passive"))
      (node (ref "R28") (pin "2") (pintype "passive"))
    )
    (net (code "65") (name "Net-(C29-Pad1)") (class "Default")
      (node (ref "C29") (pin "1") (pinfunction "1_1") (pintype "passive"))
      (node (ref "R29") (pin "2") (pintype "passive"))
      (node (ref "R30") (pin "2") (pintype "passive"))
    )
    (net (code "66") (name "Net-(D1-PadA)") (class "Default")
      (node (ref "D1") (pin "A") (pinfunction "A_A") (pintype "passive"))
      (node (ref "R3") (pin "2") (pintype "passive"))
    )
    (net (code "67") (name "Net-(D2-PadA)") (class "Default")
      (node (ref "D2") (pin "A") (pinfunction "A_A") (pintype "passive"))
      (node (ref "R8") (pin "2") (pintype "passive"))
    )
    (net (code "68") (name "Net-(D3-PadA)") (class "Default")
      (node (ref "D3") (pin "A") (pinfunction "A_A") (pintype "passive"))
      (node (ref "R11") (pin "2") (pintype "passive"))
    )
    (net (code "69") (name "Net-(D4-PadA)") (class "Default")
      (node (ref "D4") (pin "A") (pinfunction "A_A") (pintype "passive"))
      (node (ref "R12") (pin "2") (pintype "passive"))
    )
    (net (code "70") (name "Net-(D5-PadA)") (class "Default")
      (node (ref "D5") (pin "A") (pinfunction "A_A") (pintype "passive"))
      (node (ref "R14") (pin "2") (pintype "passive"))
    )
    (net (code "71") (name "Net-(D6-PadA)") (class "Default")
      (node (ref "D6") (pin "A") (pinfunction "A_A") (pintype "passive"))
      (node (ref "R15") (pin "2") (pintype "passive"))
    )
    (net (code "72") (name "Net-(D7-PadA)") (class "Default")
      (node (ref "D7") (pin "A") (pinfunction "A_A") (pintype "passive"))
      (node (ref "R19") (pin "2") (pintype "passive"))
    )
    (net (code "73") (name "Net-(D8-PadA)") (class "Default")
      (node (ref "D8") (pin "A") (pinfunction "A_A") (pintype "passive"))
      (node (ref "R21") (pin "2") (pintype "passive"))
    )
    (net (code "74") (name "Net-(J5-Pad10)") (class "Default")
      (node (ref "J5") (pin "10") (pinfunction "10_10") (pintype "passive"))
      (node (ref "R22") (pin "2") (pintype "passive"))
    )
    (net (code "75") (name "Net-(U1-BOOT0)") (class "Default")
      (node (ref "R9") (pin "1") (pintype "passive"))
      (node (ref "U1") (pin "60") (pinfunction "BOOT0_60") (pintype "input"))
    )
    (net (code "76") (name "Net-(U1-VCAP_1)") (class "Default")
      (node (ref "C14") (pin "1") (pinfunction "1_1") (pintype "passive"))
      (node (ref "C15") (pin "1") (pinfunction "1_1") (pintype "passive"))
      (node (ref "U1") (pin "30") (pinfunction "VCAP_1_30") (pintype "power_in"))
    )
  )
)
